# Blinker_Circuit_For_PCB.net
KiCad netlist of a schematic drawn in Altium Designer
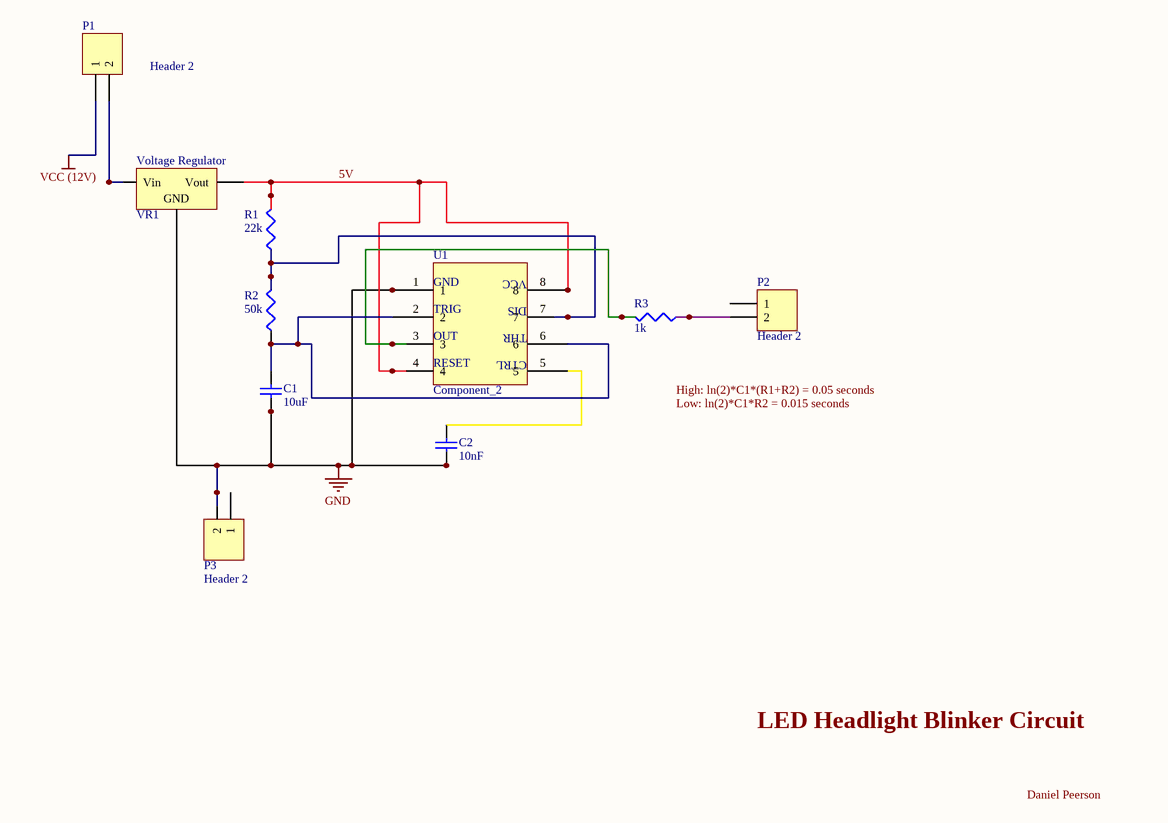
[diagram p0: Blinker_Circuit_For_PCB.SchDoc]

(export (version "E")
  (design (tool "Eeschema 10.0.6"))
  (components
    (comp (ref "C1")
      (value "10uF")
      (footprint "C1206")
      (description "Capacitor (Semiconductor SIM Model)")
      (fields (field (name "Comment") "Cap Semi") (field (name "PUBLISHER") "Altium Limited"))
      (libsource (lib "Miscellaneous Devices") (part "Cap Semi"))
    )
    (comp (ref "C2")
      (value "10nF")
      (footprint "C1206")
      (description "Capacitor (Semiconductor SIM Model)")
      (fields (field (name "Comment") "Cap Semi") (field (name "PUBLISHER") "Altium Limited"))
      (libsource (lib "Miscellaneous Devices") (part "Cap Semi"))
    )
    (comp (ref "P1")
      (value "Header 2")
      (footprint "HDR1X2")
      (description "Header, 2-Pin")
      (fields (field (name "PUBLISHER") "Altium Limited"))
      (libsource (lib "") (part "Header 2_2"))
    )
    (comp (ref "P2")
      (value "Header 2")
      (footprint "HDR1X2")
      (description "Header, 2-Pin")
      (fields (field (name "PUBLISHER") "Altium Limited"))
      (libsource (lib "") (part "Header 2_1"))
    )
    (comp (ref "P3")
      (value "Header 2")
      (footprint "HDR1X2")
      (description "Header, 2-Pin")
      (fields (field (name "PUBLISHER") "Altium Limited"))
      (libsource (lib "Miscellaneous Connectors") (part "Header 2"))
    )
    (comp (ref "R1")
      (value "22k")
      (footprint "14-1210")
      (description "Resistor")
      (fields (field (name "Comment") "Res3") (field (name "PUBLISHER") "Altium Limited"))
      (libsource (lib "Miscellaneous Devices") (part "Res3"))
    )
    (comp (ref "R2")
      (value "50k")
      (footprint "14-1210")
      (description "Resistor")
      (fields (field (name "Comment") "Res3") (field (name "PUBLISHER") "Altium Limited"))
      (libsource (lib "Miscellaneous Devices") (part "Res3"))
    )
    (comp (ref "R3")
      (value "1k")
      (footprint "14-1210")
      (description "Resistor")
      (fields (field (name "Comment") "Res3") (field (name "PUBLISHER") "Altium Limited"))
      (libsource (lib "Miscellaneous Devices") (part "Res3"))
    )
    (comp (ref "U1") (value "Component_2") (footprint "555") (libsource (lib "555") (part "Component_2")))
    (comp (ref "VR1")
      (value "Voltage Regulator")
      (footprint "D2PAK_N")
      (fields (field (name "PUBLISHER") "Altium Limited"))
      (libsource (lib "Miscellaneous Devices") (part "Volt Reg"))
    )
  )
  (nets
    (net (code "1") (name "/5V") (class "Default")
      (node (ref "R1") (pin "2") (pinfunction "2_2") (pintype "passive"))
      (node (ref "U1") (pin "4") (pinfunction "4_4") (pintype "passive"))
      (node (ref "U1") (pin "8") (pinfunction "8_8") (pintype "passive"))
      (node (ref "VR1") (pin "3") (pinfunction "Vout_3") (pintype "passive"))
    )
    (net (code "6") (name "GND") (class "Default")
      (node (ref "C1") (pin "1") (pinfunction "1_1") (pintype "passive"))
      (node (ref "C2") (pin "2") (pinfunction "2_2") (pintype "passive"))
      (node (ref "P3") (pin "2") (pinfunction "2_2") (pintype "passive"))
      (node (ref "U1") (pin "1") (pinfunction "1_1") (pintype "passive"))
      (node (ref "VR1") (pin "2") (pinfunction "GND_2") (pintype "passive"))
    )
    (net (code "7") (name "Net-(C1-Pad2)") (class "Default")
      (node (ref "C1") (pin "2") (pinfunction "2_2") (pintype "passive"))
      (node (ref "R2") (pin "1") (pinfunction "1_1") (pintype "passive"))
      (node (ref "U1") (pin "2") (pinfunction "2_2") (pintype "passive"))
      (node (ref "U1") (pin "6") (pinfunction "6_6") (pintype "passive"))
    )
    (net (code "8") (name "Net-(C2-Pad1)") (class "Default")
      (node (ref "C2") (pin "1") (pinfunction "1_1") (pintype "passive"))
      (node (ref "U1") (pin "5") (pinfunction "5_5") (pintype "passive"))
    )
    (net (code "9") (name "Net-(P2-Pad2)") (class "Default")
      (node (ref "P2") (pin "2") (pinfunction "2_2") (pintype "passive"))
      (node (ref "R3") (pin "1") (pinfunction "1_1") (pintype "passive"))
    )
    (net (code "10") (name "Net-(R1-Pad1)") (class "Default")
      (node (ref "R1") (pin "1") (pinfunction "1_1") (pintype "passive"))
      (node (ref "R2") (pin "2") (pinfunction "2_2") (pintype "passive"))
      (node (ref "U1") (pin "7") (pinfunction "7_7") (pintype "passive"))
    )
    (net (code "11") (name "Net-(R3-Pad2)") (class "Default")
      (node (ref "R3") (pin "2") (pinfunction "2_2") (pintype "passive"))
      (node (ref "U1") (pin "3") (pinfunction "3_3") (pintype "passive"))
    )
    (net (code "12") (name "Net-(VR1-Vin)") (class "Default")
      (node (ref "P1") (pin "2") (pinfunction "2_2") (pintype "passive"))
      (node (ref "VR1") (pin "1") (pinfunction "Vin_1") (pintype "passive"))
    )
    (net (code "13") (name "VCC (12V)") (class "Default")
      (node (ref "P1") (pin "1") (pinfunction "1_1") (pintype "passive"))
    )
    (net (code "14") (name "unconnected-(P2-Pad1)") (class "Default")
      (node (ref "P2") (pin "1") (pinfunction "1_1") (pintype "passive"))
    )
    (net (code "15") (name "unconnected-(P3-Pad1)") (class "Default")
      (node (ref "P3") (pin "1") (pinfunction "1_1") (pintype "passive"))
    )
  )
)
